# Sop16.net
KiCad netlist of a schematic drawn in EAGLE
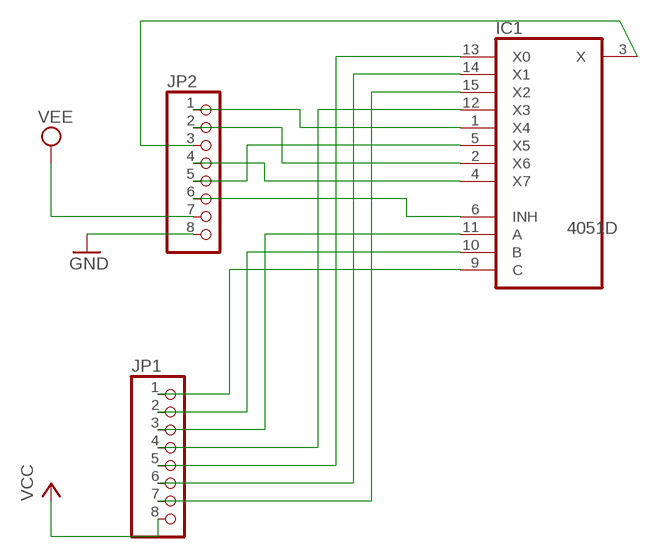
[diagram p0: schematic, sheet 1]

(export (version "E")
  (design (tool "Eeschema 10.0.6"))
  (components
    (comp (ref "IC1")
      (value "4051D")
      (footprint "eagle-import:SO16")
      (libsource (lib "eagle-import") (part "4051D"))
    )
    (comp (ref "JP1")
      (value "PINHD-1X8")
      (footprint "eagle-import:1X08")
      (libsource (lib "eagle-import") (part "PINHD-1X8"))
    )
    (comp (ref "JP2")
      (value "PINHD-1X8")
      (footprint "eagle-import:1X08")
      (libsource (lib "eagle-import") (part "PINHD-1X8"))
    )
  )
  (nets
    (net (code "1") (name "GND") (class "Default")
      (node (ref "JP2") (pin "8") (pinfunction "8_8") (pintype "passive"))
    )
    (net (code "2") (name "Net-(IC1A-A)") (class "Default")
      (node (ref "IC1") (pin "11") (pinfunction "A_11") (pintype "input"))
      (node (ref "JP1") (pin "3") (pinfunction "3_3") (pintype "passive"))
    )
    (net (code "3") (name "Net-(IC1A-B)") (class "Default")
      (node (ref "IC1") (pin "10") (pinfunction "B_10") (pintype "input"))
      (node (ref "JP1") (pin "2") (pinfunction "2_2") (pintype "passive"))
    )
    (net (code "4") (name "Net-(IC1A-C)") (class "Default")
      (node (ref "IC1") (pin "9") (pinfunction "C_9") (pintype "input"))
      (node (ref "JP1") (pin "1") (pinfunction "1_1") (pintype "passive"))
    )
    (net (code "5") (name "Net-(IC1A-INH)") (class "Default")
      (node (ref "IC1") (pin "6") (pinfunction "INH_6") (pintype "input"))
      (node (ref "JP2") (pin "6") (pinfunction "6_6") (pintype "passive"))
    )
    (net (code "6") (name "Net-(IC1A-X)") (class "Default")
      (node (ref "IC1") (pin "3") (pinfunction "X_3") (pintype "bidirectional"))
      (node (ref "JP2") (pin "3") (pinfunction "3_3") (pintype "passive"))
    )
    (net (code "7") (name "Net-(IC1A-X0)") (class "Default")
      (node (ref "IC1") (pin "13") (pinfunction "X0_13") (pintype "bidirectional"))
      (node (ref "JP1") (pin "5") (pinfunction "5_5") (pintype "passive"))
    )
    (net (code "8") (name "Net-(IC1A-X1)") (class "Default")
      (node (ref "IC1") (pin "14") (pinfunction "X1_14") (pintype "bidirectional"))
      (node (ref "JP1") (pin "6") (pinfunction "6_6") (pintype "passive"))
    )
    (net (code "9") (name "Net-(IC1A-X2)") (class "Default")
      (node (ref "IC1") (pin "15") (pinfunction "X2_15") (pintype "bidirectional"))
      (node (ref "JP1") (pin "7") (pinfunction "7_7") (pintype "passive"))
    )
    (net (code "10") (name "Net-(IC1A-X3)") (class "Default")
      (node (ref "IC1") (pin "12") (pinfunction "X3_12") (pintype "bidirectional"))
      (node (ref "JP1") (pin "4") (pinfunction "4_4") (pintype "passive"))
    )
    (net (code "11") (name "Net-(IC1A-X4)") (class "Default")
      (node (ref "IC1") (pin "1") (pinfunction "X4_1") (pintype "bidirectional"))
      (node (ref "JP2") (pin "1") (pinfunction "1_1") (pintype "passive"))
    )
    (net (code "12") (name "Net-(IC1A-X5)") (class "Default")
      (node (ref "IC1") (pin "5") (pinfunction "X5_5") (pintype "bidirectional"))
      (node (ref "JP2") (pin "5") (pinfunction "5_5") (pintype "passive"))
    )
    (net (code "13") (name "Net-(IC1A-X6)") (class "Default")
      (node (ref "IC1") (pin "2") (pinfunction "X6_2") (pintype "bidirectional"))
      (node (ref "JP2") (pin "2") (pinfunction "2_2") (pintype "passive"))
    )
    (net (code "14") (name "Net-(IC1A-X7)") (class "Default")
      (node (ref "IC1") (pin "4") (pinfunction "X7_4") (pintype "bidirectional"))
      (node (ref "JP2") (pin "4") (pinfunction "4_4") (pintype "passive"))
    )
    (net (code "15") (name "VCC") (class "Default")
      (node (ref "JP1") (pin "8") (pinfunction "8_8") (pintype "passive"))
    )
    (net (code "16") (name "VEE") (class "Default")
      (node (ref "JP2") (pin "7") (pinfunction "7_7") (pintype "passive"))
    )
  )
)
